# Switch_Panel.net
KiCad netlist of a schematic drawn in Altium Designer
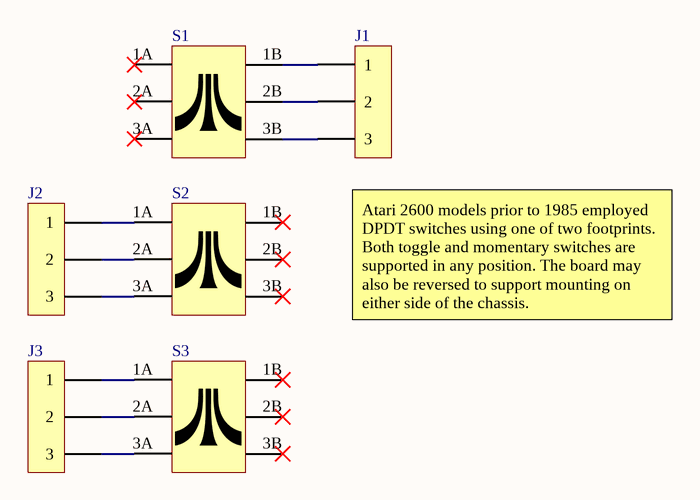
[diagram p0: Switch Panel.SchDoc]

(export (version "E")
  (design (tool "Eeschema 10.0.6"))
  (components
    (comp (ref "J1")
      (value "Switch Header")
      (footprint "HDR1X3")
      (libsource (lib "") (part "Switch Header_1"))
    )
    (comp (ref "J2")
      (value "Switch Header")
      (footprint "HDR1X3")
      (libsource (lib "Atari2600") (part "Switch Header"))
    )
    (comp (ref "J3")
      (value "Switch Header")
      (footprint "HDR1X3")
      (libsource (lib "Atari2600") (part "Switch Header"))
    )
    (comp (ref "S1")
      (value "SWITCH")
      (footprint "SWITCH")
      (description "DPDT Switch")
      (libsource (lib "Switch Panel") (part "SWITCH"))
    )
    (comp (ref "S2")
      (value "SWITCH")
      (footprint "SWITCH")
      (description "DPDT Switch")
      (libsource (lib "Switch Panel") (part "SWITCH"))
    )
    (comp (ref "S3")
      (value "SWITCH")
      (footprint "SWITCH")
      (description "DPDT Switch")
      (libsource (lib "Switch Panel") (part "SWITCH"))
    )
  )
  (nets
    (net (code "1") (name "Net-(J1-Pad1)") (class "Default")
      (node (ref "J1") (pin "1") (pinfunction "1_1") (pintype "passive"))
      (node (ref "S1") (pin "1B") (pinfunction "1B_1B") (pintype "passive"))
    )
    (net (code "2") (name "Net-(J1-Pad2)") (class "Default")
      (node (ref "J1") (pin "2") (pinfunction "2_2") (pintype "passive"))
      (node (ref "S1") (pin "2B") (pinfunction "2B_2B") (pintype "passive"))
    )
    (net (code "3") (name "Net-(J1-Pad3)") (class "Default")
      (node (ref "J1") (pin "3") (pinfunction "3_3") (pintype "passive"))
      (node (ref "S1") (pin "3B") (pinfunction "3B_3B") (pintype "passive"))
    )
    (net (code "4") (name "Net-(J2-Pad1)") (class "Default")
      (node (ref "J2") (pin "1") (pinfunction "1_1") (pintype "passive"))
      (node (ref "S2") (pin "1A") (pinfunction "1A_1A") (pintype "passive"))
    )
    (net (code "5") (name "Net-(J2-Pad2)") (class "Default")
      (node (ref "J2") (pin "2") (pinfunction "2_2") (pintype "passive"))
      (node (ref "S2") (pin "2A") (pinfunction "2A_2A") (pintype "passive"))
    )
    (net (code "6") (name "Net-(J2-Pad3)") (class "Default")
      (node (ref "J2") (pin "3") (pinfunction "3_3") (pintype "passive"))
      (node (ref "S2") (pin "3A") (pinfunction "3A_3A") (pintype "passive"))
    )
    (net (code "7") (name "Net-(J3-Pad1)") (class "Default")
      (node (ref "J3") (pin "1") (pinfunction "1_1") (pintype "passive"))
      (node (ref "S3") (pin "1A") (pinfunction "1A_1A") (pintype "passive"))
    )
    (net (code "8") (name "Net-(J3-Pad2)") (class "Default")
      (node (ref "J3") (pin "2") (pinfunction "2_2") (pintype "passive"))
      (node (ref "S3") (pin "2A") (pinfunction "2A_2A") (pintype "passive"))
    )
    (net (code "9") (name "Net-(J3-Pad3)") (class "Default")
      (node (ref "J3") (pin "3") (pinfunction "3_3") (pintype "passive"))
      (node (ref "S3") (pin "3A") (pinfunction "3A_3A") (pintype "passive"))
    )
    (net (code "10") (name "unconnected-(S1-Pad1A)") (class "Default")
      (node (ref "S1") (pin "1A") (pinfunction "1A_1A") (pintype "passive+no_connect"))
    )
    (net (code "11") (name "unconnected-(S1-Pad2A)") (class "Default")
      (node (ref "S1") (pin "2A") (pinfunction "2A_2A") (pintype "passive+no_connect"))
    )
    (net (code "12") (name "unconnected-(S1-Pad3A)") (class "Default")
      (node (ref "S1") (pin "3A") (pinfunction "3A_3A") (pintype "passive+no_connect"))
    )
    (net (code "13") (name "unconnected-(S2-Pad1B)") (class "Default")
      (node (ref "S2") (pin "1B") (pinfunction "1B_1B") (pintype "passive+no_connect"))
    )
    (net (code "14") (name "unconnected-(S2-Pad2B)") (class "Default")
      (node (ref "S2") (pin "2B") (pinfunction "2B_2B") (pintype "passive+no_connect"))
    )
    (net (code "15") (name "unconnected-(S2-Pad3B)") (class "Default")
      (node (ref "S2") (pin "3B") (pinfunction "3B_3B") (pintype "passive+no_connect"))
    )
    (net (code "16") (name "unconnected-(S3-Pad1B)") (class "Default")
      (node (ref "S3") (pin "1B") (pinfunction "1B_1B") (pintype "passive+no_connect"))
    )
    (net (code "17") (name "unconnected-(S3-Pad2B)") (class "Default")
      (node (ref "S3") (pin "2B") (pinfunction "2B_2B") (pintype "passive+no_connect"))
    )
    (net (code "18") (name "unconnected-(S3-Pad3B)") (class "Default")
      (node (ref "S3") (pin "3B") (pinfunction "3B_3B") (pintype "passive+no_connect"))
    )
  )
)
